# schema2.net
KiCad netlist of a schematic drawn in Altium Designer
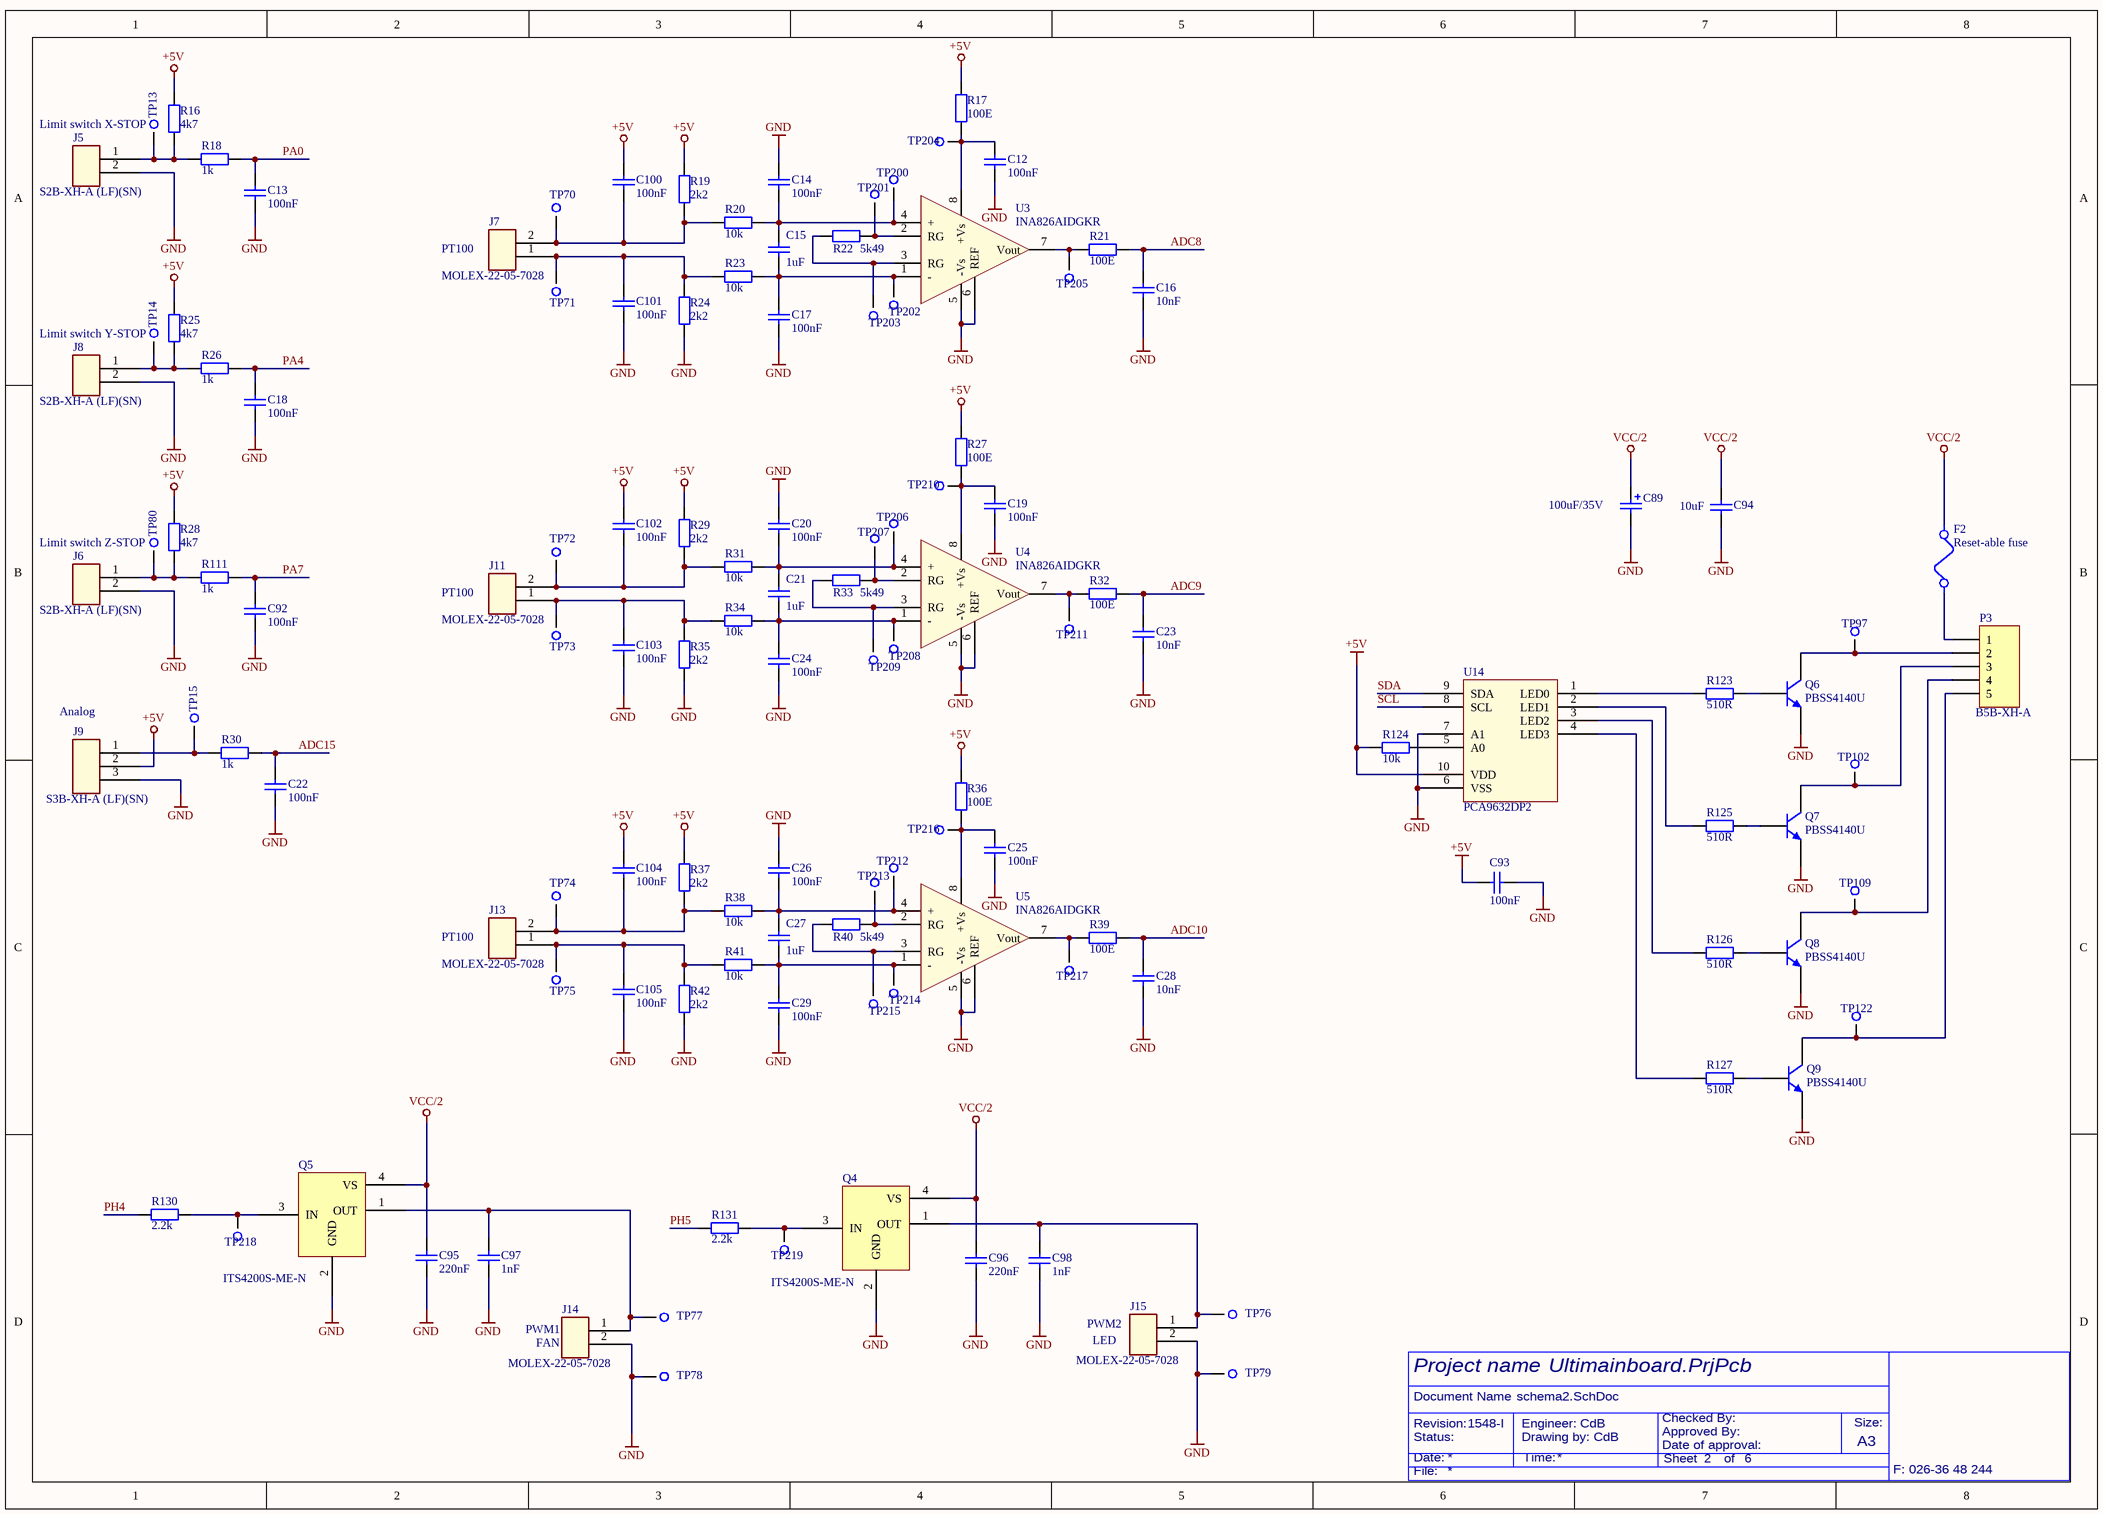
[diagram p0: schema2.SchDoc]

(export (version "E")
  (design (tool "Eeschema 10.0.6"))
  (components
    (comp (ref "C12")
      (value "100nF")
      (footprint "C0603")
      (description "RO X7R 100nF 10% 50V 0603")
      (libsource (lib "Database_Faber") (part "Capacitor"))
    )
    (comp (ref "C13")
      (value "100nF")
      (footprint "C0603")
      (description "RO X7R 100nF 10% 50V 0603")
      (libsource (lib "Database_Faber") (part "Capacitor"))
    )
    (comp (ref "C14")
      (value "100nF")
      (footprint "C0603")
      (description "RO X7R 100nF 10% 50V 0603")
      (libsource (lib "Database_Faber") (part "Capacitor"))
    )
    (comp (ref "C15")
      (value "1uF")
      (footprint "C0603")
      (description "RO X5R 1uF 10% 10V 0603")
      (libsource (lib "Database_Faber") (part "Capacitor"))
    )
    (comp (ref "C16")
      (value "10nF")
      (footprint "C0603")
      (description "RO X7R 10nF 10% 50V 0603")
      (libsource (lib "Database_Faber") (part "Capacitor"))
    )
    (comp (ref "C17")
      (value "100nF")
      (footprint "C0603")
      (description "RO X7R 100nF 10% 50V 0603")
      (libsource (lib "Database_Faber") (part "Capacitor"))
    )
    (comp (ref "C18")
      (value "100nF")
      (footprint "C0603")
      (description "RO X7R 100nF 10% 50V 0603")
      (libsource (lib "Database_Faber") (part "Capacitor"))
    )
    (comp (ref "C19")
      (value "100nF")
      (footprint "C0603")
      (description "RO X7R 100nF 10% 50V 0603")
      (libsource (lib "Database_Faber") (part "Capacitor"))
    )
    (comp (ref "C20")
      (value "100nF")
      (footprint "C0603")
      (description "RO X7R 100nF 10% 50V 0603")
      (libsource (lib "Database_Faber") (part "Capacitor"))
    )
    (comp (ref "C21")
      (value "1uF")
      (footprint "C0603")
      (description "RO X5R 1uF 10% 10V 0603")
      (libsource (lib "Database_Faber") (part "Capacitor"))
    )
    (comp (ref "C22")
      (value "100nF")
      (footprint "C0603")
      (description "RO X7R 100nF 10% 50V 0603")
      (libsource (lib "Database_Faber") (part "Capacitor"))
    )
    (comp (ref "C23")
      (value "10nF")
      (footprint "C0603")
      (description "RO X7R 10nF 10% 50V 0603")
      (libsource (lib "Database_Faber") (part "Capacitor"))
    )
    (comp (ref "C24")
      (value "100nF")
      (footprint "C0603")
      (description "RO X7R 100nF 10% 50V 0603")
      (libsource (lib "Database_Faber") (part "Capacitor"))
    )
    (comp (ref "C25")
      (value "100nF")
      (footprint "C0603")
      (description "RO X7R 100nF 10% 50V 0603")
      (libsource (lib "Database_Faber") (part "Capacitor"))
    )
    (comp (ref "C26")
      (value "100nF")
      (footprint "C0603")
      (description "RO X7R 100nF 10% 50V 0603")
      (libsource (lib "Database_Faber") (part "Capacitor"))
    )
    (comp (ref "C27")
      (value "1uF")
      (footprint "C0603")
      (description "RO X5R 1uF 10% 10V 0603")
      (libsource (lib "Database_Faber") (part "Capacitor"))
    )
    (comp (ref "C28")
      (value "10nF")
      (footprint "C0603")
      (description "RO X7R 10nF 10% 50V 0603")
      (libsource (lib "Database_Faber") (part "Capacitor"))
    )
    (comp (ref "C29")
      (value "100nF")
      (footprint "C0603")
      (description "RO X7R 100nF 10% 50V 0603")
      (libsource (lib "Database_Faber") (part "Capacitor"))
    )
    (comp (ref "C89")
      (value "100uF/35V")
      (footprint "ELCO Case D")
      (description "RO ELCO 100uF 20% 35V CASE-D EEEFP PAN")
      (libsource (lib "Database_Faber") (part "Capacitor Polarity"))
    )
    (comp (ref "C92")
      (value "100nF")
      (footprint "C0603")
      (description "RO X7R 100nF 10% 50V 0603")
      (libsource (lib "Database_Faber") (part "Capacitor"))
    )
    (comp (ref "C93")
      (value "100nF")
      (footprint "C0805")
      (description "Cap 100nF X7R 0805 10% 100V")
      (fields (field (name "MFG") "AVX"))
      (libsource (lib "Faber_SCH_lib") (part "Cap 100nF X7R 0805"))
    )
    (comp (ref "C94")
      (value "10uF")
      (footprint "C1206")
      (description "RO X5R 10UF 10% 35V 1206")
      (libsource (lib "Database_Faber") (part "Capacitor"))
    )
    (comp (ref "C95")
      (value "220nF")
      (footprint "C0805")
      (description "Capacitor, C Series, 0.22 µF, ± 10%, X7R, 50 V, 0805 [2012 Metric]")
      (fields (field (name "MFG") "KEMET"))
      (libsource (lib "Miscellaneous Devices") (part "Cap"))
    )
    (comp (ref "C96")
      (value "220nF")
      (footprint "C0805")
      (description "Capacitor, C Series, 0.22 µF, ± 10%, X7R, 50 V, 0805 [2012 Metric]")
      (fields (field (name "MFG") "KEMET"))
      (libsource (lib "Miscellaneous Devices") (part "Cap"))
    )
    (comp (ref "C97")
      (value "1nF")
      (footprint "C0603")
      (description "CAP X7R 1nF 10% 50V 0603")
      (fields (field (name "MFG") "WALSIN"))
      (libsource (lib "Database_Faber") (part "Capacitor"))
    )
    (comp (ref "C98")
      (value "1nF")
      (footprint "C0603")
      (description "CAP X7R 1nF 10% 50V 0603")
      (fields (field (name "MFG") "WALSIN"))
      (libsource (lib "Database_Faber") (part "Capacitor"))
    )
    (comp (ref "C100")
      (value "100nF")
      (footprint "C0603")
      (description "RO X7R 100nF 10% 50V 0603")
      (libsource (lib "Database_Faber") (part "Capacitor"))
    )
    (comp (ref "C101")
      (value "100nF")
      (footprint "C0603")
      (description "RO X7R 100nF 10% 50V 0603")
      (libsource (lib "Database_Faber") (part "Capacitor"))
    )
    (comp (ref "C102")
      (value "100nF")
      (footprint "C0603")
      (description "RO X7R 100nF 10% 50V 0603")
      (libsource (lib "Database_Faber") (part "Capacitor"))
    )
    (comp (ref "C103")
      (value "100nF")
      (footprint "C0603")
      (description "RO X7R 100nF 10% 50V 0603")
      (libsource (lib "Database_Faber") (part "Capacitor"))
    )
    (comp (ref "C104")
      (value "100nF")
      (footprint "C0603")
      (description "RO X7R 100nF 10% 50V 0603")
      (libsource (lib "Database_Faber") (part "Capacitor"))
    )
    (comp (ref "C105")
      (value "100nF")
      (footprint "C0603")
      (description "RO X7R 100nF 10% 50V 0603")
      (libsource (lib "Database_Faber") (part "Capacitor"))
    )
    (comp (ref "F2")
      (value "Reset-able fuse")
      (footprint "Bourns reset-able fuse")
      (fields (field (name "MFG") "Bourns"))
      (libsource (lib "Database_Faber") (part "Multifuse"))
    )
    (comp (ref "J5")
      (value "S2B-XH-A (LF)(SN)")
      (footprint "S2B-XH-A (LF)(SN)")
      (description "RO CONN PR 2p HKS S2B-XH-A (LF)(SN) JST")
      (fields (field (name "MFG") "JST (JAPAN SOLDERLESS TERMINALS)"))
      (libsource (lib "Database_Faber") (part "HEADER 2"))
    )
    (comp (ref "J6")
      (value "S2B-XH-A (LF)(SN)")
      (footprint "S2B-XH-A (LF)(SN)")
      (description "RO CONN PR 2p HKS S2B-XH-A (LF)(SN) JST")
      (fields (field (name "MFG") "JST (JAPAN SOLDERLESS TERMINALS)"))
      (libsource (lib "Database_Faber") (part "HEADER 2"))
    )
    (comp (ref "J7")
      (value "MOLEX-22-05-7028")
      (footprint "MOLEX-22-05-7028")
      (description "RO CONN PR 2p HKS 22-05-7028 MOLEX")
      (fields (field (name "MFG") "MOLEX"))
      (libsource (lib "") (part "HEADER 2_1"))
    )
    (comp (ref "J8")
      (value "S2B-XH-A (LF)(SN)")
      (footprint "S2B-XH-A (LF)(SN)")
      (description "RO CONN PR 2p HKS S2B-XH-A (LF)(SN) JST")
      (fields (field (name "MFG") "JST (JAPAN SOLDERLESS TERMINALS)"))
      (libsource (lib "Database_Faber") (part "HEADER 2"))
    )
    (comp (ref "J9")
      (value "S3B-XH-A (LF)(SN)")
      (footprint "S3B-XH-A (LF)(SN)")
      (description "RO CONN PR 3p HKS S3B-XH-A (LF)(SN) JST")
      (fields (field (name "MFG") "JST (JAPAN SOLDERLESS TERMINALS)"))
      (libsource (lib "Database_Faber") (part "HEADER 3"))
    )
    (comp (ref "J11")
      (value "MOLEX-22-05-7028")
      (footprint "MOLEX-22-05-7028")
      (description "RO CONN PR 2p HKS 22-05-7028 MOLEX")
      (fields (field (name "MFG") "MOLEX"))
      (libsource (lib "") (part "HEADER 2_1"))
    )
    (comp (ref "J13")
      (value "MOLEX-22-05-7028")
      (footprint "MOLEX-22-05-7028")
      (description "RO CONN PR 2p HKS 22-05-7028 MOLEX")
      (fields (field (name "MFG") "MOLEX"))
      (libsource (lib "") (part "HEADER 2_1"))
    )
    (comp (ref "J14")
      (value "MOLEX-22-05-7028")
      (footprint "MOLEX-22-05-7028")
      (description "RO CONN PR 2p HKS 22-05-7028 MOLEX")
      (fields (field (name "MFG") "MOLEX"))
      (libsource (lib "Database_Faber") (part "HEADER 2"))
    )
    (comp (ref "J15")
      (value "MOLEX-22-05-7028")
      (footprint "MOLEX-22-05-7028")
      (description "RO CONN PR 2p HKS 22-05-7028 MOLEX")
      (fields (field (name "MFG") "MOLEX"))
      (libsource (lib "Database_Faber") (part "HEADER 2"))
    )
    (comp (ref "P3")
      (value "B5B-XH-A")
      (footprint "B5B-XH-A")
      (description "Header, 5-Pin")
      (fields
        (field (name "MFG") "JST (JAPAN SOLDERLESS TERMINALS)")
        (field (name "PUBLISHER") "Altium Limited")
      )
      (libsource (lib "Miscellaneous Connectors") (part "Header 5"))
    )
    (comp (ref "Q4")
      (value "ITS4200S-ME-N")
      (footprint "SOT223 Smartfet")
      (description "Infeneon ITS4200S-ME-N")
      (fields (field (name "MFG") "Infineon"))
      (libsource (lib "Ultimainboard") (part "MOSFET-N met GND"))
    )
    (comp (ref "Q5")
      (value "ITS4200S-ME-N")
      (footprint "SOT223 Smartfet")
      (description "Infeneon ITS4200S-ME-N")
      (fields (field (name "MFG") "Infineon"))
      (libsource (lib "Ultimainboard") (part "MOSFET-N met GND"))
    )
    (comp (ref "Q6")
      (value "PBSS4140U")
      (footprint "SOT65P210X110-3N")
      (description "NPN PBSS4140U SOT-323 1A")
      (fields (field (name "MFG") "NXP"))
      (libsource (lib "Faber_SCH_lib") (part "NPN PBSS4140U"))
    )
    (comp (ref "Q7")
      (value "PBSS4140U")
      (footprint "SOT65P210X110-3N")
      (description "NPN PBSS4140U SOT-323 1A")
      (fields (field (name "MFG") "NXP"))
      (libsource (lib "Faber_SCH_lib") (part "NPN PBSS4140U"))
    )
    (comp (ref "Q8")
      (value "PBSS4140U")
      (footprint "SOT65P210X110-3N")
      (description "NPN PBSS4140U SOT-323 1A")
      (fields (field (name "MFG") "NXP"))
      (libsource (lib "Faber_SCH_lib") (part "NPN PBSS4140U"))
    )
    (comp (ref "Q9")
      (value "PBSS4140U")
      (footprint "SOT65P210X110-3N")
      (description "NPN PBSS4140U SOT-323 1A")
      (fields (field (name "MFG") "NXP"))
      (libsource (lib "Faber_SCH_lib") (part "NPN PBSS4140U"))
    )
    (comp (ref "R16")
      (value "4k7")
      (footprint "R0603")
      (description "RO RES 4k70 1% 0,063W  0603")
      (libsource (lib "") (part "Resistor_3"))
    )
    (comp (ref "R17")
      (value "100E")
      (footprint "R0603")
      (description "RO RES 100E 1% 0,063W  0603")
      (libsource (lib "") (part "Resistor_1"))
    )
    (comp (ref "R18")
      (value "1k")
      (footprint "R0603")
      (description "RO RES 1k0 1% 0,1W  0603")
      (libsource (lib "") (part "Resistor_2"))
    )
    (comp (ref "R19")
      (value "2k2")
      (footprint "R0603")
      (description "RO RES 2k2 0,1% 0,063W 25ppm 0603")
      (fields (field (name "MFG") "TE CONNECTIVITY / NEOHM"))
      (libsource (lib "") (part "Resistor_1"))
    )
    (comp (ref "R20")
      (value "10k")
      (footprint "R0603")
      (description "RO RES 10k0 1% 0,063W  0603")
      (libsource (lib "") (part "Resistor_2"))
    )
    (comp (ref "R21")
      (value "100E")
      (footprint "R0603")
      (description "RO RES 100E 1% 0,063W  0603")
      (libsource (lib "") (part "Resistor_2"))
    )
    (comp (ref "R22")
      (value "5k49")
      (footprint "R0603")
      (description "RO RES 5K49 0,1% 0,063W 25ppm 0603")
      (fields (field (name "MFG") "WELWYN"))
      (libsource (lib "Database_Faber") (part "Resistor"))
    )
    (comp (ref "R23")
      (value "10k")
      (footprint "R0603")
      (description "RO RES 10k0 1% 0,063W  0603")
      (libsource (lib "") (part "Resistor_2"))
    )
    (comp (ref "R24")
      (value "2k2")
      (footprint "R0603")
      (description "RO RES 2k2 0,1% 0,063W 25ppm 0603")
      (fields (field (name "MFG") "TE CONNECTIVITY / NEOHM"))
      (libsource (lib "") (part "Resistor_3"))
    )
    (comp (ref "R25")
      (value "4k7")
      (footprint "R0603")
      (description "RO RES 4k70 1% 0,063W  0603")
      (libsource (lib "") (part "Resistor_3"))
    )
    (comp (ref "R26")
      (value "1k")
      (footprint "R0603")
      (description "RO RES 1k0 1% 0,1W  0603")
      (libsource (lib "") (part "Resistor_2"))
    )
    (comp (ref "R27")
      (value "100E")
      (footprint "R0603")
      (description "RO RES 100E 1% 0,063W  0603")
      (libsource (lib "") (part "Resistor_1"))
    )
    (comp (ref "R28")
      (value "4k7")
      (footprint "R0603")
      (description "RO RES 4k70 1% 0,063W  0603")
      (libsource (lib "") (part "Resistor_3"))
    )
    (comp (ref "R29")
      (value "2k2")
      (footprint "R0603")
      (description "RO RES 2k2 0,1% 0,063W 25ppm 0603")
      (fields (field (name "MFG") "TE CONNECTIVITY / NEOHM"))
      (libsource (lib "") (part "Resistor_1"))
    )
    (comp (ref "R30")
      (value "1k")
      (footprint "R0603")
      (description "RO RES 1k0 1% 0,1W  0603")
      (libsource (lib "") (part "Resistor_2"))
    )
    (comp (ref "R31")
      (value "10k")
      (footprint "R0603")
      (description "RO RES 10k0 1% 0,063W  0603")
      (libsource (lib "") (part "Resistor_2"))
    )
    (comp (ref "R32")
      (value "100E")
      (footprint "R0603")
      (description "RO RES 100E 1% 0,063W  0603")
      (libsource (lib "") (part "Resistor_2"))
    )
    (comp (ref "R33")
      (value "5k49")
      (footprint "R0603")
      (description "RO RES 5K49 0,1% 0,063W 25ppm 0603")
      (fields (field (name "MFG") "WELWYN"))
      (libsource (lib "Database_Faber") (part "Resistor"))
    )
    (comp (ref "R34")
      (value "10k")
      (footprint "R0603")
      (description "RO RES 10k0 1% 0,063W  0603")
      (libsource (lib "") (part "Resistor_2"))
    )
    (comp (ref "R35")
      (value "2k2")
      (footprint "R0603")
      (description "RO RES 2k2 0,1% 0,063W 25ppm 0603")
      (fields (field (name "MFG") "TE CONNECTIVITY / NEOHM"))
      (libsource (lib "") (part "Resistor_3"))
    )
    (comp (ref "R36")
      (value "100E")
      (footprint "R0603")
      (description "RO RES 100E 1% 0,063W  0603")
      (libsource (lib "") (part "Resistor_1"))
    )
    (comp (ref "R37")
      (value "2k2")
      (footprint "R0603")
      (description "RO RES 2k2 0,1% 0,063W 25ppm 0603")
      (fields (field (name "MFG") "TE CONNECTIVITY / NEOHM"))
      (libsource (lib "") (part "Resistor_1"))
    )
    (comp (ref "R38")
      (value "10k")
      (footprint "R0603")
      (description "RO RES 10k0 1% 0,063W  0603")
      (libsource (lib "") (part "Resistor_2"))
    )
    (comp (ref "R39")
      (value "100E")
      (footprint "R0603")
      (description "RO RES 100E 1% 0,063W  0603")
      (libsource (lib "") (part "Resistor_2"))
    )
    (comp (ref "R40")
      (value "5k49")
      (footprint "R0603")
      (description "RO RES 5K49 0,1% 0,063W 25ppm 0603")
      (fields (field (name "MFG") "WELWYN"))
      (libsource (lib "Database_Faber") (part "Resistor"))
    )
    (comp (ref "R41")
      (value "10k")
      (footprint "R0603")
      (description "RO RES 10k0 1% 0,063W  0603")
      (libsource (lib "") (part "Resistor_2"))
    )
    (comp (ref "R42")
      (value "2k2")
      (footprint "R0603")
      (description "RO RES 2k2 0,1% 0,063W 25ppm 0603")
      (fields (field (name "MFG") "TE CONNECTIVITY / NEOHM"))
      (libsource (lib "") (part "Resistor_3"))
    )
    (comp (ref "R111")
      (value "1k")
      (footprint "R0603")
      (description "RO RES 1k0 1% 0,1W  0603")
      (libsource (lib "") (part "Resistor_2"))
    )
    (comp (ref "R123")
      (value "510R")
      (footprint "R0603")
      (description "RO RES 510R 1% 0,063W  0603")
      (fields (field (name "MFG") "MULTICOMP"))
      (libsource (lib "Database_Faber") (part "Resistor"))
    )
    (comp (ref "R124")
      (value "10k")
      (footprint "R0603")
      (description "RO RES 10k0 1% 0,063W  0603")
      (libsource (lib "Database_Faber") (part "Resistor"))
    )
    (comp (ref "R125")
      (value "510R")
      (footprint "R0603")
      (description "RO RES 510R 1% 0,063W  0603")
      (fields (field (name "MFG") "MULTICOMP"))
      (libsource (lib "Database_Faber") (part "Resistor"))
    )
    (comp (ref "R126")
      (value "510R")
      (footprint "R0603")
      (description "RO RES 510R 1% 0,063W  0603")
      (fields (field (name "MFG") "MULTICOMP"))
      (libsource (lib "Database_Faber") (part "Resistor"))
    )
    (comp (ref "R127")
      (value "510R")
      (footprint "R0603")
      (description "RO RES 510R 1% 0,063W  0603")
      (fields (field (name "MFG") "MULTICOMP"))
      (libsource (lib "Database_Faber") (part "Resistor"))
    )
    (comp (ref "R130")
      (value "2.2k")
      (footprint "RESC1608X05N")
      (description "RES 2.20K OHM 1/10W 1% 0603 SMD")
      (fields
        (field (name "MANUFACTURER") "Vishay Dale")
        (field (name "MANUFACTURER PART NUMBER") "CRCW06032K20FKEA")
      )
      (libsource (lib "Marlin") (part "2.2k/0603"))
    )
    (comp (ref "R131")
      (value "2.2k")
      (footprint "RESC1608X05N")
      (description "RES 2.20K OHM 1/10W 1% 0603 SMD")
      (fields
        (field (name "MANUFACTURER") "Vishay Dale")
        (field (name "MANUFACTURER PART NUMBER") "CRCW06032K20FKEA")
      )
      (libsource (lib "Marlin") (part "2.2k/0603"))
    )
    (comp (ref "TP13")
      (value "Testpoint")
      (footprint "Testpoint")
      (libsource (lib "Database_Faber") (part "Testpoint"))
    )
    (comp (ref "TP14")
      (value "Testpoint")
      (footprint "Testpoint")
      (libsource (lib "Database_Faber") (part "Testpoint"))
    )
    (comp (ref "TP15")
      (value "Testpoint")
      (footprint "Testpoint")
      (libsource (lib "Database_Faber") (part "Testpoint"))
    )
    (comp (ref "TP70")
      (value "Testpoint")
      (footprint "Testpoint")
      (libsource (lib "Database_Faber") (part "Testpoint"))
    )
    (comp (ref "TP71")
      (value "Testpoint")
      (footprint "Testpoint")
      (libsource (lib "Database_Faber") (part "Testpoint"))
    )
    (comp (ref "TP72")
      (value "Testpoint")
      (footprint "Testpoint")
      (libsource (lib "Database_Faber") (part "Testpoint"))
    )
    (comp (ref "TP73")
      (value "Testpoint")
      (footprint "Testpoint")
      (libsource (lib "Database_Faber") (part "Testpoint"))
    )
    (comp (ref "TP74")
      (value "Testpoint")
      (footprint "Testpoint")
      (libsource (lib "Database_Faber") (part "Testpoint"))
    )
    (comp (ref "TP75")
      (value "Testpoint")
      (footprint "Testpoint")
      (libsource (lib "Database_Faber") (part "Testpoint"))
    )
    (comp (ref "TP76")
      (value "Testpoint")
      (footprint "Testpoint")
      (libsource (lib "Database_Faber") (part "Testpoint"))
    )
    (comp (ref "TP77")
      (value "Testpoint")
      (footprint "Testpoint")
      (libsource (lib "Database_Faber") (part "Testpoint"))
    )
    (comp (ref "TP78")
      (value "Testpoint")
      (footprint "Testpoint")
      (libsource (lib "Database_Faber") (part "Testpoint"))
    )
    (comp (ref "TP79")
      (value "Testpoint")
      (footprint "Testpoint")
      (libsource (lib "Database_Faber") (part "Testpoint"))
    )
    (comp (ref "TP80")
      (value "Testpoint")
      (footprint "Testpoint")
      (libsource (lib "Database_Faber") (part "Testpoint"))
    )
    (comp (ref "TP97")
      (value "2mm")
      (footprint "TESTPOINT")
      (description "Testpoint, 2mm, round")
      (libsource (lib "Faber_SCH_lib") (part "Testpoint, 2mm, round"))
    )
    (comp (ref "TP102")
      (value "2mm")
      (footprint "TESTPOINT")
      (description "Testpoint, 2mm, round")
      (libsource (lib "Faber_SCH_lib") (part "Testpoint, 2mm, round"))
    )
    (comp (ref "TP109")
      (value "2mm")
      (footprint "TESTPOINT")
      (description "Testpoint, 2mm, round")
      (libsource (lib "Faber_SCH_lib") (part "Testpoint, 2mm, round"))
    )
    (comp (ref "TP122")
      (value "2mm")
      (footprint "TESTPOINT")
      (description "Testpoint, 2mm, round")
      (libsource (lib "Faber_SCH_lib") (part "Testpoint, 2mm, round"))
    )
    (comp (ref "TP200")
      (value "Testpoint 1.6mm")
      (footprint "Testpoint 1.6mm")
      (libsource (lib "Ultimaker") (part "Testpoint 1.6mm"))
    )
    (comp (ref "TP201")
      (value "Testpoint 1.6mm")
      (footprint "Testpoint 1.6mm")
      (libsource (lib "Ultimaker") (part "Testpoint 1.6mm"))
    )
    (comp (ref "TP202")
      (value "Testpoint 1.6mm")
      (footprint "Testpoint 1.6mm")
      (libsource (lib "Ultimaker") (part "Testpoint 1.6mm"))
    )
    (comp (ref "TP203")
      (value "Testpoint 1.6mm")
      (footprint "Testpoint 1.6mm")
      (libsource (lib "Ultimaker") (part "Testpoint 1.6mm"))
    )
    (comp (ref "TP204")
      (value "Testpoint 1.6mm")
      (footprint "Testpoint 1.6mm")
      (libsource (lib "Ultimaker") (part "Testpoint 1.6mm"))
    )
    (comp (ref "TP205")
      (value "Testpoint 1.6mm")
      (footprint "Testpoint 1.6mm")
      (libsource (lib "Ultimaker") (part "Testpoint 1.6mm"))
    )
    (comp (ref "TP206")
      (value "Testpoint 1.6mm")
      (footprint "Testpoint 1.6mm")
      (libsource (lib "Ultimaker") (part "Testpoint 1.6mm"))
    )
    (comp (ref "TP207")
      (value "Testpoint 1.6mm")
      (footprint "Testpoint 1.6mm")
      (libsource (lib "Ultimaker") (part "Testpoint 1.6mm"))
    )
    (comp (ref "TP208")
      (value "Testpoint 1.6mm")
      (footprint "Testpoint 1.6mm")
      (libsource (lib "Ultimaker") (part "Testpoint 1.6mm"))
    )
    (comp (ref "TP209")
      (value "Testpoint 1.6mm")
      (footprint "Testpoint 1.6mm")
      (libsource (lib "Ultimaker") (part "Testpoint 1.6mm"))
    )
    (comp (ref "TP210")
      (value "Testpoint 1.6mm")
      (footprint "Testpoint 1.6mm")
      (libsource (lib "Ultimaker") (part "Testpoint 1.6mm"))
    )
    (comp (ref "TP211")
      (value "Testpoint 1.6mm")
      (footprint "Testpoint 1.6mm")
      (libsource (lib "Ultimaker") (part "Testpoint 1.6mm"))
    )
    (comp (ref "TP212")
      (value "Testpoint 1.6mm")
      (footprint "Testpoint 1.6mm")
      (libsource (lib "Ultimaker") (part "Testpoint 1.6mm"))
    )
    (comp (ref "TP213")
      (value "Testpoint 1.6mm")
      (footprint "Testpoint 1.6mm")
      (libsource (lib "Ultimaker") (part "Testpoint 1.6mm"))
    )
    (comp (ref "TP214")
      (value "Testpoint 1.6mm")
      (footprint "Testpoint 1.6mm")
      (libsource (lib "Ultimaker") (part "Testpoint 1.6mm"))
    )
    (comp (ref "TP215")
      (value "Testpoint 1.6mm")
      (footprint "Testpoint 1.6mm")
      (libsource (lib "Ultimaker") (part "Testpoint 1.6mm"))
    )
    (comp (ref "TP216")
      (value "Testpoint 1.6mm")
      (footprint "Testpoint 1.6mm")
      (libsource (lib "Ultimaker") (part "Testpoint 1.6mm"))
    )
    (comp (ref "TP217")
      (value "Testpoint 1.6mm")
      (footprint "Testpoint 1.6mm")
      (libsource (lib "Ultimaker") (part "Testpoint 1.6mm"))
    )
    (comp (ref "TP218")
      (value "Testpoint 1.6mm")
      (footprint "Testpoint 1.6mm")
      (libsource (lib "Ultimaker") (part "Testpoint 1.6mm"))
    )
    (comp (ref "TP219")
      (value "Testpoint 1.6mm")
      (footprint "Testpoint 1.6mm")
      (libsource (lib "Ultimaker") (part "Testpoint 1.6mm"))
    )
    (comp (ref "U3")
      (value "INA826AIDGKR")
      (footprint "TSOP65P490X110-8N (MSOP8)")
      (description "RO IC INA826AIDGKR MSOP-8 TI")
      (fields (field (name "MFG") "Texas Instruments"))
      (libsource (lib "Database_Faber") (part "INA826AIDGKR"))
    )
    (comp (ref "U4")
      (value "INA826AIDGKR")
      (footprint "TSOP65P490X110-8N (MSOP8)")
      (description "RO IC INA826AIDGKR MSOP-8 TI")
      (fields (field (name "MFG") "Texas Instruments"))
      (libsource (lib "Database_Faber") (part "INA826AIDGKR"))
    )
    (comp (ref "U5")
      (value "INA826AIDGKR")
      (footprint "TSOP65P490X110-8N (MSOP8)")
      (description "RO IC INA826AIDGKR MSOP-8 TI")
      (fields (field (name "MFG") "Texas Instruments"))
      (libsource (lib "Database_Faber") (part "INA826AIDGKR"))
    )
    (comp (ref "U14")
      (value "PCA9632DP2")
      (footprint "IC TSSOP-10")
      (description "IC LED DRIVER RGBA")
      (fields (field (name "MFG") "NXP"))
      (libsource (lib "Faber_SCH_lib") (part "IC PCA9632"))
    )
  )
  (nets
    (net (code "1") (name "+5V") (class "Default")
      (node (ref "C100") (pin "2") (pinfunction "2_2") (pintype "passive"))
      (node (ref "C102") (pin "2") (pinfunction "2_2") (pintype "passive"))
      (node (ref "C104") (pin "2") (pinfunction "2_2") (pintype "passive"))
      (node (ref "C93") (pin "1") (pinfunction "1_1") (pintype "passive"))
      (node (ref "J9") (pin "2") (pinfunction "2_2") (pintype "passive"))
      (node (ref "R124") (pin "2") (pinfunction "2_2") (pintype "passive"))
      (node (ref "R16") (pin "2") (pinfunction "2_2") (pintype "passive"))
      (node (ref "R17") (pin "1") (pinfunction "1_1") (pintype "passive"))
      (node (ref "R19") (pin "1") (pinfunction "1_1") (pintype "passive"))
      (node (ref "R25") (pin "2") (pinfunction "2_2") (pintype "passive"))
      (node (ref "R27") (pin "1") (pinfunction "1_1") (pintype "passive"))
      (node (ref "R28") (pin "2") (pinfunction "2_2") (pintype "passive"))
      (node (ref "R29") (pin "1") (pinfunction "1_1") (pintype "passive"))
      (node (ref "R36") (pin "1") (pinfunction "1_1") (pintype "passive"))
      (node (ref "R37") (pin "1") (pinfunction "1_1") (pintype "passive"))
      (node (ref "U14") (pin "10") (pinfunction "VDD_10") (pintype "passive"))
    )
    (net (code "2") (name "/ADC8") (class "Default")
      (node (ref "C16") (pin "2") (pinfunction "2_2") (pintype "passive"))
      (node (ref "R21") (pin "2") (pinfunction "2_2") (pintype "passive"))
    )
    (net (code "3") (name "/ADC9") (class "Default")
      (node (ref "C23") (pin "2") (pinfunction "2_2") (pintype "passive"))
      (node (ref "R32") (pin "2") (pinfunction "2_2") (pintype "passive"))
    )
    (net (code "4") (name "/ADC10") (class "Default")
      (node (ref "C28") (pin "2") (pinfunction "2_2") (pintype "passive"))
      (node (ref "R39") (pin "2") (pinfunction "2_2") (pintype "passive"))
    )
    (net (code "5") (name "/ADC15") (class "Default")
      (node (ref "C22") (pin "2") (pinfunction "2_2") (pintype "passive"))
      (node (ref "R30") (pin "2") (pinfunction "2_2") (pintype "passive"))
    )
    (net (code "6") (name "/PA0") (class "Default")
      (node (ref "C13") (pin "2") (pinfunction "2_2") (pintype "passive"))
      (node (ref "R18") (pin "2") (pinfunction "2_2") (pintype "passive"))
    )
    (net (code "7") (name "/PA4") (class "Default")
      (node (ref "C18") (pin "2") (pinfunction "2_2") (pintype "passive"))
      (node (ref "R26") (pin "2") (pinfunction "2_2") (pintype "passive"))
    )
    (net (code "8") (name "/PA7") (class "Default")
      (node (ref "C92") (pin "2") (pinfunction "2_2") (pintype "passive"))
      (node (ref "R111") (pin "2") (pinfunction "2_2") (pintype "passive"))
    )
    (net (code "9") (name "/PH4") (class "Default")
      (node (ref "R130") (pin "2") (pinfunction "2_2") (pintype "passive"))
    )
    (net (code "10") (name "/PH5") (class "Default")
      (node (ref "R131") (pin "2") (pinfunction "2_2") (pintype "passive"))
    )
    (net (code "11") (name "/SCL") (class "Default")
      (node (ref "U14") (pin "8") (pinfunction "SCL_8") (pintype "passive"))
    )
    (net (code "12") (name "/SDA") (class "Default")
      (node (ref "U14") (pin "9") (pinfunction "SDA_9") (pintype "passive"))
    )
    (net (code "13") (name "GND") (class "Default")
      (node (ref "C101") (pin "1") (pinfunction "1_1") (pintype "passive"))
      (node (ref "C103") (pin "1") (pinfunction "1_1") (pintype "passive"))
      (node (ref "C105") (pin "1") (pinfunction "1_1") (pintype "passive"))
      (node (ref "C12") (pin "1") (pinfunction "1_1") (pintype "passive"))
      (node (ref "C13") (pin "1") (pinfunction "1_1") (pintype "passive"))
      (node (ref "C14") (pin "2") (pinfunction "2_2") (pintype "passive"))
      (node (ref "C16") (pin "1") (pinfunction "1_1") (pintype "passive"))
      (node (ref "C17") (pin "1") (pinfunction "1_1") (pintype "passive"))
      (node (ref "C18") (pin "1") (pinfunction "1_1") (pintype "passive"))
      (node (ref "C19") (pin "1") (pinfunction "1_1") (pintype "passive"))
      (node (ref "C20") (pin "2") (pinfunction "2_2") (pintype "passive"))
      (node (ref "C22") (pin "1") (pinfunction "1_1") (pintype "passive"))
      (node (ref "C23") (pin "1") (pinfunction "1_1") (pintype "passive"))
      (node (ref "C24") (pin "1") (pinfunction "1_1") (pintype "passive"))
      (node (ref "C25") (pin "1") (pinfunction "1_1") (pintype "passive"))
      (node (ref "C26") (pin "2") (pinfunction "2_2") (pintype "passive"))
      (node (ref "C28") (pin "1") (pinfunction "1_1") (pintype "passive"))
      (node (ref "C29") (pin "1") (pinfunction "1_1") (pintype "passive"))
      (node (ref "C89") (pin "2") (pinfunction "2_2") (pintype "passive"))
      (node (ref "C92") (pin "1") (pinfunction "1_1") (pintype "passive"))
      (node (ref "C93") (pin "2") (pinfunction "2_2") (pintype "passive"))
      (node (ref "C94") (pin "1") (pinfunction "1_1") (pintype "passive"))
      (node (ref "C95") (pin "1") (pinfunction "1_1") (pintype "passive"))
      (node (ref "C96") (pin "1") (pinfunction "1_1") (pintype "passive"))
      (node (ref "C97") (pin "1") (pinfunction "1_1") (pintype "passive"))
      (node (ref "C98") (pin "1") (pinfunction "1_1") (pintype "passive"))
      (node (ref "J14") (pin "2") (pinfunction "2_2") (pintype "passive"))
      (node (ref "J15") (pin "2") (pinfunction "2_2") (pintype "passive"))
      (node (ref "J5") (pin "2") (pinfunction "2_2") (pintype "passive"))
      (node (ref "J6") (pin "2") (pinfunction "2_2") (pintype "passive"))
      (node (ref "J8") (pin "2") (pinfunction "2_2") (pintype "passive"))
      (node (ref "J9") (pin "3") (pinfunction "3_3") (pintype "passive"))
      (node (ref "Q4") (pin "2") (pinfunction "GND_2") (pintype "passive"))
      (node (ref "Q5") (pin "2") (pinfunction "GND_2") (pintype "passive"))
      (node (ref "Q6") (pin "2") (pinfunction "E_2") (pintype "passive"))
      (node (ref "Q7") (pin "2") (pinfunction "E_2") (pintype "passive"))
      (node (ref "Q8") (pin "2") (pinfunction "E_2") (pintype "passive"))
      (node (ref "Q9") (pin "2") (pinfunction "E_2") (pintype "passive"))
      (node (ref "R24") (pin "1") (pinfunction "1_1") (pintype "passive"))
      (node (ref "R35") (pin "1") (pinfunction "1_1") (pintype "passive"))
      (node (ref "R42") (pin "1") (pinfunction "1_1") (pintype "passive"))
      (node (ref "TP78") (pin "1") (pinfunction "1_1") (pintype "passive"))
      (node (ref "TP79") (pin "1") (pinfunction "1_1") (pintype "passive"))
      (node (ref "U14") (pin "6") (pinfunction "VSS_6") (pintype "passive"))
      (node (ref "U14") (pin "7") (pinfunction "A1_7") (pintype "passive"))
      (node (ref "U3") (pin "5") (pinfunction "-Vs_5") (pintype "passive"))
      (node (ref "U3") (pin "6") (pinfunction "REF_6") (pintype "passive"))
      (node (ref "U4") (pin "5") (pinfunction "-Vs_5") (pintype "passive"))
      (node (ref "U4") (pin "6") (pinfunction "REF_6") (pintype "passive"))
      (node (ref "U5") (pin "5") (pinfunction "-Vs_5") (pintype "passive"))
      (node (ref "U5") (pin "6") (pinfunction "REF_6") (pintype "passive"))
    )
    (net (code "14") (name "Net-(C100-Pad1)") (class "Default")
      (node (ref "C100") (pin "1") (pinfunction "1_1") (pintype "passive"))
      (node (ref "J7") (pin "2") (pinfunction "2_2") (pintype "passive"))
      (node (ref "R19") (pin "2") (pinfunction "2_2") (pintype "passive"))
      (node (ref "R20") (pin "1") (pinfunction "1_1") (pintype "passive"))
      (node (ref "TP70") (pin "1") (pinfunction "1_1") (pintype "passive"))
    )
    (net (code "15") (name "Net-(C101-Pad2)") (class "Default")
      (node (ref "C101") (pin "2") (pinfunction "2_2") (pintype "passive"))
      (node (ref "J7") (pin "1") (pinfunction "1_1") (pintype "passive"))
      (node (ref "R23") (pin "1") (pinfunction "1_1") (pintype "passive"))
      (node (ref "R24") (pin "2") (pinfunction "2_2") (pintype "passive"))
      (node (ref "TP71") (pin "1") (pinfunction "1_1") (pintype "passive"))
    )
    (net (code "16") (name "Net-(C102-Pad1)") (class "Default")
      (node (ref "C102") (pin "1") (pinfunction "1_1") (pintype "passive"))
      (node (ref "J11") (pin "2") (pinfunction "2_2") (pintype "passive"))
      (node (ref "R29") (pin "2") (pinfunction "2_2") (pintype "passive"))
      (node (ref "R31") (pin "1") (pinfunction "1_1") (pintype "passive"))
      (node (ref "TP72") (pin "1") (pinfunction "1_1") (pintype "passive"))
    )
    (net (code "17") (name "Net-(C103-Pad2)") (class "Default")
      (node (ref "C103") (pin "2") (pinfunction "2_2") (pintype "passive"))
      (node (ref "J11") (pin "1") (pinfunction "1_1") (pintype "passive"))
      (node (ref "R34") (pin "1") (pinfunction "1_1") (pintype "passive"))
      (node (ref "R35") (pin "2") (pinfunction "2_2") (pintype "passive"))
      (node (ref "TP73") (pin "1") (pinfunction "1_1") (pintype "passive"))
    )
    (net (code "18") (name "Net-(C104-Pad1)") (class "Default")
      (node (ref "C104") (pin "1") (pinfunction "1_1") (pintype "passive"))
      (node (ref "J13") (pin "2") (pinfunction "2_2") (pintype "passive"))
      (node (ref "R37") (pin "2") (pinfunction "2_2") (pintype "passive"))
      (node (ref "R38") (pin "1") (pinfunction "1_1") (pintype "passive"))
      (node (ref "TP74") (pin "1") (pinfunction "1_1") (pintype "passive"))
    )
    (net (code "19") (name "Net-(C105-Pad2)") (class "Default")
      (node (ref "C105") (pin "2") (pinfunction "2_2") (pintype "passive"))
      (node (ref "J13") (pin "1") (pinfunction "1_1") (pintype "passive"))
      (node (ref "R41") (pin "1") (pinfunction "1_1") (pintype "passive"))
      (node (ref "R42") (pin "2") (pinfunction "2_2") (pintype "passive"))
      (node (ref "TP75") (pin "1") (pinfunction "1_1") (pintype "passive"))
    )
    (net (code "20") (name "Net-(F2-Pad1)") (class "Default")
      (node (ref "F2") (pin "1") (pinfunction "1_1") (pintype "passive"))
      (node (ref "P3") (pin "1") (pinfunction "1_1") (pintype "passive"))
    )
    (net (code "21") (name "Net-(J5-Pad1)") (class "Default")
      (node (ref "J5") (pin "1") (pinfunction "1_1") (pintype "passive"))
      (node (ref "R16") (pin "1") (pinfunction "1_1") (pintype "passive"))
      (node (ref "R18") (pin "1") (pinfunction "1_1") (pintype "passive"))
      (node (ref "TP13") (pin "1") (pinfunction "1_1") (pintype "passive"))
    )
    (net (code "22") (name "Net-(J6-Pad1)") (class "Default")
      (node (ref "J6") (pin "1") (pinfunction "1_1") (pintype "passive"))
      (node (ref "R111") (pin "1") (pinfunction "1_1") (pintype "passive"))
      (node (ref "R28") (pin "1") (pinfunction "1_1") (pintype "passive"))
      (node (ref "TP80") (pin "1") (pinfunction "1_1") (pintype "passive"))
    )
    (net (code "23") (name "Net-(J8-Pad1)") (class "Default")
      (node (ref "J8") (pin "1") (pinfunction "1_1") (pintype "passive"))
      (node (ref "R25") (pin "1") (pinfunction "1_1") (pintype "passive"))
      (node (ref "R26") (pin "1") (pinfunction "1_1") (pintype "passive"))
      (node (ref "TP14") (pin "1") (pinfunction "1_1") (pintype "passive"))
    )
    (net (code "24") (name "Net-(J9-Pad1)") (class "Default")
      (node (ref "J9") (pin "1") (pinfunction "1_1") (pintype "passive"))
      (node (ref "R30") (pin "1") (pinfunction "1_1") (pintype "passive"))
      (node (ref "TP15") (pin "1") (pinfunction "1_1") (pintype "passive"))
    )
    (net (code "25") (name "Net-(Q4-IN)") (class "Default")
      (node (ref "Q4") (pin "3") (pinfunction "IN_3") (pintype "passive"))
      (node (ref "R131") (pin "1") (pinfunction "1_1") (pintype "passive"))
      (node (ref "TP219") (pin "1") (pinfunction "1_1") (pintype "passive"))
    )
    (net (code "26") (name "Net-(Q4-OUT)") (class "Default")
      (node (ref "C98") (pin "2") (pinfunction "2_2") (pintype "passive"))
      (node (ref "J15") (pin "1") (pinfunction "1_1") (pintype "passive"))
      (node (ref "Q4") (pin "1") (pinfunction "OUT_1") (pintype "passive"))
      (node (ref "TP76") (pin "1") (pinfunction "1_1") (pintype "passive"))
    )
    (net (code "27") (name "Net-(Q5-IN)") (class "Default")
      (node (ref "Q5") (pin "3") (pinfunction "IN_3") (pintype "passive"))
      (node (ref "R130") (pin "1") (pinfunction "1_1") (pintype "passive"))
      (node (ref "TP218") (pin "1") (pinfunction "1_1") (pintype "passive"))
    )
    (net (code "28") (name "Net-(Q5-OUT)") (class "Default")
      (node (ref "C97") (pin "2") (pinfunction "2_2") (pintype "passive"))
      (node (ref "J14") (pin "1") (pinfunction "1_1") (pintype "passive"))
      (node (ref "Q5") (pin "1") (pinfunction "OUT_1") (pintype "passive"))
      (node (ref "TP77") (pin "1") (pinfunction "1_1") (pintype "passive"))
    )
    (net (code "29") (name "Net-(Q6-B)") (class "Default")
      (node (ref "Q6") (pin "1") (pinfunction "B_1") (pintype "passive"))
      (node (ref "R123") (pin "1") (pinfunction "1_1") (pintype "passive"))
    )
    (net (code "30") (name "Net-(Q6-C)") (class "Default")
      (node (ref "P3") (pin "2") (pinfunction "2_2") (pintype "passive"))
      (node (ref "Q6") (pin "3") (pinfunction "C_3") (pintype "passive"))
      (node (ref "TP97") (pin "1") (pinfunction "1_1") (pintype "passive"))
    )
    (net (code "31") (name "Net-(Q7-B)") (class "Default")
      (node (ref "Q7") (pin "1") (pinfunction "B_1") (pintype "passive"))
      (node (ref "R125") (pin "1") (pinfunction "1_1") (pintype "passive"))
    )
    (net (code "32") (name "Net-(Q7-C)") (class "Default")
      (node (ref "P3") (pin "3") (pinfunction "3_3") (pintype "passive"))
      (node (ref "Q7") (pin "3") (pinfunction "C_3") (pintype "passive"))
      (node (ref "TP102") (pin "1") (pinfunction "1_1") (pintype "passive"))
    )
    (net (code "33") (name "Net-(Q8-B)") (class "Default")
      (node (ref "Q8") (pin "1") (pinfunction "B_1") (pintype "passive"))
      (node (ref "R126") (pin "1") (pinfunction "1_1") (pintype "passive"))
    )
    (net (code "34") (name "Net-(Q8-C)") (class "Default")
      (node (ref "P3") (pin "4") (pinfunction "4_4") (pintype "passive"))
      (node (ref "Q8") (pin "3") (pinfunction "C_3") (pintype "passive"))
      (node (ref "TP109") (pin "1") (pinfunction "1_1") (pintype "passive"))
    )
    (net (code "35") (name "Net-(Q9-B)") (class "Default")
      (node (ref "Q9") (pin "1") (pinfunction "B_1") (pintype "passive"))
      (node (ref "R127") (pin "1") (pinfunction "1_1") (pintype "passive"))
    )
    (net (code "36") (name "Net-(Q9-C)") (class "Default")
      (node (ref "P3") (pin "5") (pinfunction "5_5") (pintype "passive"))
      (node (ref "Q9") (pin "3") (pinfunction "C_3") (pintype "passive"))
      (node (ref "TP122") (pin "1") (pinfunction "1_1") (pintype "passive"))
    )
    (net (code "37") (name "Net-(R22-Pad1)") (class "Default")
      (node (ref "R22") (pin "1") (pinfunction "1_1") (pintype "passive"))
      (node (ref "TP201") (pin "1") (pinfunction "1_1") (pintype "passive"))
      (node (ref "U3") (pin "2") (pinfunction "RG_2") (pintype "passive"))
    )
    (net (code "38") (name "Net-(R22-Pad2)") (class "Default")
      (node (ref "R22") (pin "2") (pinfunction "2_2") (pintype "passive"))
      (node (ref "TP203") (pin "1") (pinfunction "1_1") (pintype "passive"))
      (node (ref "U3") (pin "3") (pinfunction "RG_3") (pintype "passive"))
    )
    (net (code "39") (name "Net-(R33-Pad1)") (class "Default")
      (node (ref "R33") (pin "1") (pinfunction "1_1") (pintype "passive"))
      (node (ref "TP207") (pin "1") (pinfunction "1_1") (pintype "passive"))
      (node (ref "U4") (pin "2") (pinfunction "RG_2") (pintype "passive"))
    )
    (net (code "40") (name "Net-(R33-Pad2)") (class "Default")
      (node (ref "R33") (pin "2") (pinfunction "2_2") (pintype "passive"))
      (node (ref "TP209") (pin "1") (pinfunction "1_1") (pintype "passive"))
      (node (ref "U4") (pin "3") (pinfunction "RG_3") (pintype "passive"))
    )
    (net (code "41") (name "Net-(R40-Pad1)") (class "Default")
      (node (ref "R40") (pin "1") (pinfunction "1_1") (pintype "passive"))
      (node (ref "TP213") (pin "1") (pinfunction "1_1") (pintype "passive"))
      (node (ref "U5") (pin "2") (pinfunction "RG_2") (pintype "passive"))
    )
    (net (code "42") (name "Net-(R40-Pad2)") (class "Default")
      (node (ref "R40") (pin "2") (pinfunction "2_2") (pintype "passive"))
      (node (ref "TP215") (pin "1") (pinfunction "1_1") (pintype "passive"))
      (node (ref "U5") (pin "3") (pinfunction "RG_3") (pintype "passive"))
    )
    (net (code "43") (name "Net-(U3-+)") (class "Default")
      (node (ref "C14") (pin "1") (pinfunction "1_1") (pintype "passive"))
      (node (ref "C15") (pin "2") (pinfunction "2_2") (pintype "passive"))
      (node (ref "R20") (pin "2") (pinfunction "2_2") (pintype "passive"))
      (node (ref "TP200") (pin "1") (pinfunction "1_1") (pintype "passive"))
      (node (ref "U3") (pin "4") (pinfunction "+_4") (pintype "passive"))
    )
    (net (code "44") (name "Net-(U3-+Vs)") (class "Default")
      (node (ref "C12") (pin "2") (pinfunction "2_2") (pintype "passive"))
      (node (ref "R17") (pin "2") (pinfunction "2_2") (pintype "passive"))
      (node (ref "TP204") (pin "1") (pinfunction "1_1") (pintype "passive"))
      (node (ref "U3") (pin "8") (pinfunction "+Vs_8") (pintype "passive"))
    )
    (net (code "45") (name "Net-(U3--)") (class "Default")
      (node (ref "C15") (pin "1") (pinfunction "1_1") (pintype "passive"))
      (node (ref "C17") (pin "2") (pinfunction "2_2") (pintype "passive"))
      (node (ref "R23") (pin "2") (pinfunction "2_2") (pintype "passive"))
      (node (ref "TP202") (pin "1") (pinfunction "1_1") (pintype "passive"))
      (node (ref "U3") (pin "1") (pinfunction "-_1") (pintype "passive"))
    )
    (net (code "46") (name "Net-(U3-Vout)") (class "Default")
      (node (ref "R21") (pin "1") (pinfunction "1_1") (pintype "passive"))
      (node (ref "TP205") (pin "1") (pinfunction "1_1") (pintype "passive"))
      (node (ref "U3") (pin "7") (pinfunction "Vout_7") (pintype "passive"))
    )
    (net (code "47") (name "Net-(U4-+)") (class "Default")
      (node (ref "C20") (pin "1") (pinfunction "1_1") (pintype "passive"))
      (node (ref "C21") (pin "2") (pinfunction "2_2") (pintype "passive"))
      (node (ref "R31") (pin "2") (pinfunction "2_2") (pintype "passive"))
      (node (ref "TP206") (pin "1") (pinfunction "1_1") (pintype "passive"))
      (node (ref "U4") (pin "4") (pinfunction "+_4") (pintype "passive"))
    )
    (net (code "48") (name "Net-(U4-+Vs)") (class "Default")
      (node (ref "C19") (pin "2") (pinfunction "2_2") (pintype "passive"))
      (node (ref "R27") (pin "2") (pinfunction "2_2") (pintype "passive"))
      (node (ref "TP210") (pin "1") (pinfunction "1_1") (pintype "passive"))
      (node (ref "U4") (pin "8") (pinfunction "+Vs_8") (pintype "passive"))
    )
    (net (code "49") (name "Net-(U4--)") (class "Default")
      (node (ref "C21") (pin "1") (pinfunction "1_1") (pintype "passive"))
      (node (ref "C24") (pin "2") (pinfunction "2_2") (pintype "passive"))
      (node (ref "R34") (pin "2") (pinfunction "2_2") (pintype "passive"))
      (node (ref "TP208") (pin "1") (pinfunction "1_1") (pintype "passive"))
      (node (ref "U4") (pin "1") (pinfunction "-_1") (pintype "passive"))
    )
    (net (code "50") (name "Net-(U4-Vout)") (class "Default")
      (node (ref "R32") (pin "1") (pinfunction "1_1") (pintype "passive"))
      (node (ref "TP211") (pin "1") (pinfunction "1_1") (pintype "passive"))
      (node (ref "U4") (pin "7") (pinfunction "Vout_7") (pintype "passive"))
    )
    (net (code "51") (name "Net-(U5-+)") (class "Default")
      (node (ref "C26") (pin "1") (pinfunction "1_1") (pintype "passive"))
      (node (ref "C27") (pin "2") (pinfunction "2_2") (pintype "passive"))
      (node (ref "R38") (pin "2") (pinfunction "2_2") (pintype "passive"))
      (node (ref "TP212") (pin "1") (pinfunction "1_1") (pintype "passive"))
      (node (ref "U5") (pin "4") (pinfunction "+_4") (pintype "passive"))
    )
    (net (code "52") (name "Net-(U5-+Vs)") (class "Default")
      (node (ref "C25") (pin "2") (pinfunction "2_2") (pintype "passive"))
      (node (ref "R36") (pin "2") (pinfunction "2_2") (pintype "passive"))
      (node (ref "TP216") (pin "1") (pinfunction "1_1") (pintype "passive"))
      (node (ref "U5") (pin "8") (pinfunction "+Vs_8") (pintype "passive"))
    )
    (net (code "53") (name "Net-(U5--)") (class "Default")
      (node (ref "C27") (pin "1") (pinfunction "1_1") (pintype "passive"))
      (node (ref "C29") (pin "2") (pinfunction "2_2") (pintype "passive"))
      (node (ref "R41") (pin "2") (pinfunction "2_2") (pintype "passive"))
      (node (ref "TP214") (pin "1") (pinfunction "1_1") (pintype "passive"))
      (node (ref "U5") (pin "1") (pinfunction "-_1") (pintype "passive"))
    )
    (net (code "54") (name "Net-(U5-Vout)") (class "Default")
      (node (ref "R39") (pin "1") (pinfunction "1_1") (pintype "passive"))
      (node (ref "TP217") (pin "1") (pinfunction "1_1") (pintype "passive"))
      (node (ref "U5") (pin "7") (pinfunction "Vout_7") (pintype "passive"))
    )
    (net (code "55") (name "Net-(U14-A0)") (class "Default")
      (node (ref "R124") (pin "1") (pinfunction "1_1") (pintype "passive"))
      (node (ref "U14") (pin "5") (pinfunction "A0_5") (pintype "passive"))
    )
    (net (code "56") (name "Net-(U14-LED0)") (class "Default")
      (node (ref "R123") (pin "2") (pinfunction "2_2") (pintype "passive"))
      (node (ref "U14") (pin "1") (pinfunction "LED0_1") (pintype "passive"))
    )
    (net (code "57") (name "Net-(U14-LED1)") (class "Default")
      (node (ref "R125") (pin "2") (pinfunction "2_2") (pintype "passive"))
      (node (ref "U14") (pin "2") (pinfunction "LED1_2") (pintype "passive"))
    )
    (net (code "58") (name "Net-(U14-LED2)") (class "Default")
      (node (ref "R126") (pin "2") (pinfunction "2_2") (pintype "passive"))
      (node (ref "U14") (pin "3") (pinfunction "LED2_3") (pintype "passive"))
    )
    (net (code "59") (name "Net-(U14-LED3)") (class "Default")
      (node (ref "R127") (pin "2") (pinfunction "2_2") (pintype "passive"))
      (node (ref "U14") (pin "4") (pinfunction "LED3_4") (pintype "passive"))
    )
    (net (code "60") (name "VCC{slash}2") (class "Default")
      (node (ref "C89") (pin "1") (pinfunction "1_1") (pintype "passive"))
      (node (ref "C94") (pin "2") (pinfunction "2_2") (pintype "passive"))
      (node (ref "C95") (pin "2") (pinfunction "2_2") (pintype "passive"))
      (node (ref "C96") (pin "2") (pinfunction "2_2") (pintype "passive"))
      (node (ref "F2") (pin "2") (pinfunction "2_2") (pintype "passive"))
      (node (ref "Q4") (pin "4") (pinfunction "VS_4") (pintype "passive"))
      (node (ref "Q5") (pin "4") (pinfunction "VS_4") (pintype "passive"))
    )
  )
)
